# CH595X-R0.net
KiCad netlist of a schematic drawn in Altium Designer
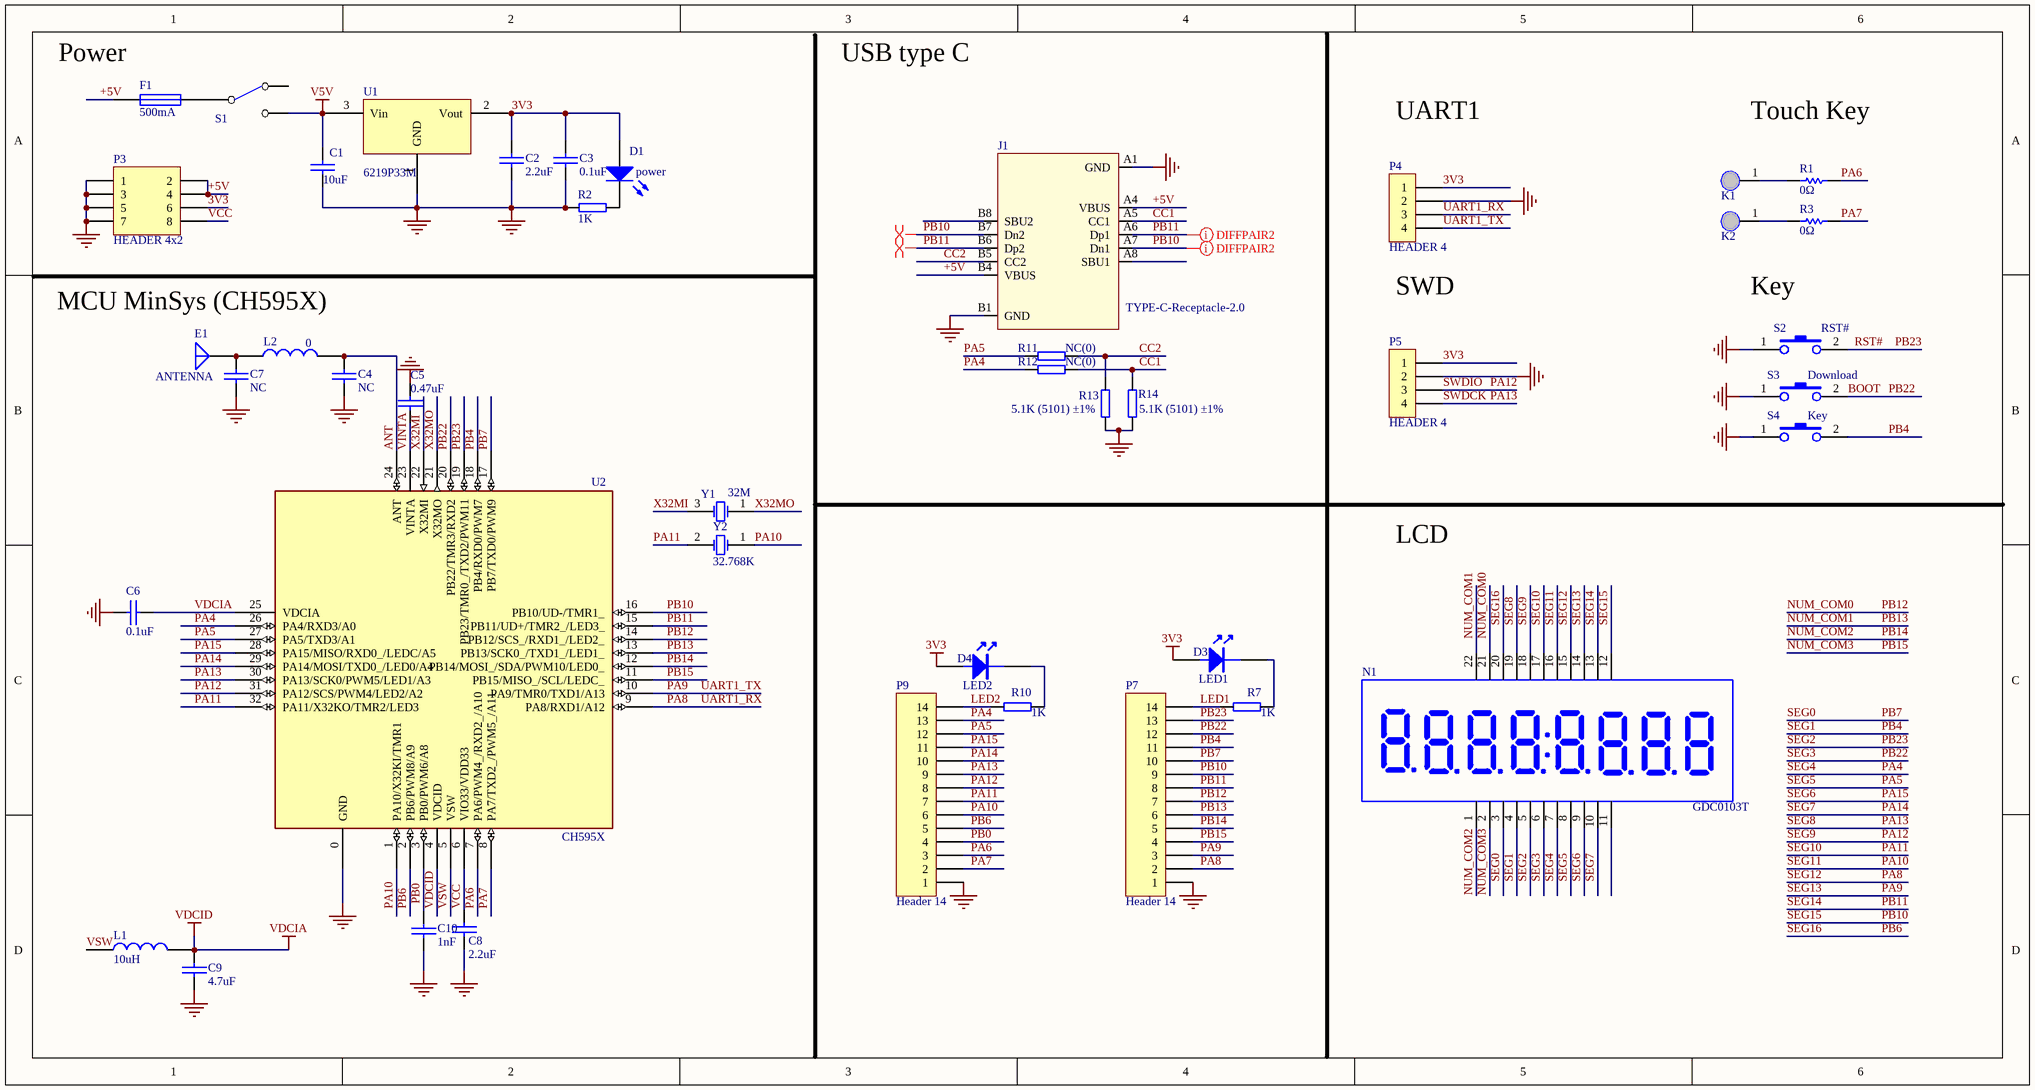
[diagram p0: CH595X-R0.SchDoc]

(export (version "E")
  (design (tool "Eeschema 10.0.6"))
  (components
    (comp (ref "C1")
      (value "10uF")
      (footprint "0603_C")
      (description "Capacitor")
      (libsource (lib "") (part "CAP_1"))
    )
    (comp (ref "C2")
      (value "2.2uF")
      (footprint "0402_C")
      (description "Capacitor")
      (libsource (lib "") (part "CAP_1"))
    )
    (comp (ref "C3")
      (value "0.1uF")
      (footprint "0402_C")
      (description "Capacitor")
      (libsource (lib "") (part "CAP_1"))
    )
    (comp (ref "C4")
      (value "NC")
      (footprint "0402_C")
      (description "Capacitor")
      (libsource (lib "*") (part "CAP"))
    )
    (comp (ref "C5")
      (value "0.47uF")
      (footprint "0402_C")
      (description "Capacitor")
      (libsource (lib "*") (part "CAP"))
    )
    (comp (ref "C6")
      (value "0.1uF")
      (footprint "0402_C")
      (description "Capacitor")
      (libsource (lib "*") (part "CAP"))
    )
    (comp (ref "C7")
      (value "NC")
      (footprint "0402_C")
      (description "Capacitor")
      (libsource (lib "*") (part "CAP"))
    )
    (comp (ref "C8")
      (value "2.2uF")
      (footprint "0402_C")
      (description "Capacitor")
      (libsource (lib "*") (part "CAP"))
    )
    (comp (ref "C9")
      (value "4.7uF")
      (footprint "0402_C")
      (description "Capacitor")
      (libsource (lib "*") (part "CAP"))
    )
    (comp (ref "C10")
      (value "1nF")
      (footprint "0402_C")
      (description "Capacitor")
      (libsource (lib "*") (part "CAP"))
    )
    (comp (ref "D1")
      (value "power")
      (footprint "0603+")
      (description "Typical INFRARED GaAs LED")
      (fields (field (name "PUBLISHER") "Altium Limited"))
      (libsource (lib "*") (part "LED0"))
    )
    (comp (ref "D3") (value "LED1") (footprint "0603+") (libsource (lib "*") (part "LED")))
    (comp (ref "D4") (value "LED2") (footprint "0603+") (libsource (lib "*") (part "LED")))
    (comp (ref "E1")
      (value "ANTENNA")
      (footprint "ANT-F-1-2.4G-1.6mmFR4")
      (description "Generic Antenna")
      (libsource (lib "*") (part "ANTENNA"))
    )
    (comp (ref "F1")
      (value "500mA")
      (footprint "0603")
      (description "Fuse")
      (libsource (lib "wch_sch_others") (part "FUSE1"))
    )
    (comp (ref "J1")
      (value "TYPE-C-Receptacle-2.0")
      (footprint "TYPE-C-Receptacle-2.0")
      (description "Type-C USB2.0 母座")
      (libsource (lib "Miscellaneous SCH Lib") (part "TYPE-C-Receptacle-2.0"))
    )
    (comp (ref "K1")
      (value "TOUCHKEY")
      (footprint "TOUCHKEY-13.6mm-S")
      (libsource (lib "wch_sch_others") (part "TOUCHKEY"))
    )
    (comp (ref "K2")
      (value "TOUCHKEY")
      (footprint "TOUCHKEY-13.6mm-S")
      (libsource (lib "wch_sch_others") (part "TOUCHKEY"))
    )
    (comp (ref "L1") (value "10uH") (footprint "SMD_2x2mm") (libsource (lib "*") (part "INDUCTOR")))
    (comp (ref "L2") (value "0") (footprint "0402") (libsource (lib "*") (part "INDUCTOR")))
    (comp (ref "N1") (value "GDC0103T") (footprint "EDC103") (libsource (lib "*") (part "EDC103")))
    (comp (ref "P3")
      (value "HEADER 4x2")
      (footprint "MYPCB:IDC8-2.54mm")
      (description "Header, 4-Pin, Dual row")
      (libsource (lib "wch_sch_others") (part "HEADER 4x2"))
    )
    (comp (ref "P4")
      (value "HEADER 4")
      (footprint "SIP4-2.54mm")
      (libsource (lib "wch_sch_others") (part "HEADER 4"))
    )
    (comp (ref "P5")
      (value "HEADER 4")
      (footprint "SIP4-2.54mm")
      (libsource (lib "wch_sch_others") (part "HEADER 4"))
    )
    (comp (ref "P7")
      (value "Header 14")
      (footprint "SIP14-2.54mm")
      (description "Header, 14-Pin")
      (fields (field (name "PUBLISHER") "Altium Limited"))
      (libsource (lib "Miscellaneous Connectors") (part "Header 14"))
    )
    (comp (ref "P9")
      (value "Header 14")
      (footprint "SIP14-2.54mm")
      (description "Header, 14-Pin")
      (fields (field (name "PUBLISHER") "Altium Limited"))
      (libsource (lib "Miscellaneous Connectors") (part "Header 14"))
    )
    (comp (ref "R1")
      (value "0Ω")
      (footprint "0402")
      (description "Semiconductor Resistor")
      (fields (field (name "PUBLISHER") "Altium Limited"))
      (libsource (lib "Miscellaneous Devices") (part "Res Semi"))
    )
    (comp (ref "R2") (value "1K") (footprint "0402") (libsource (lib "wch_sch_others") (part "RES")))
    (comp (ref "R3")
      (value "0Ω")
      (footprint "0402")
      (description "Semiconductor Resistor")
      (fields (field (name "PUBLISHER") "Altium Limited"))
      (libsource (lib "Miscellaneous Devices") (part "Res Semi"))
    )
    (comp (ref "R7") (value "1K") (footprint "0402") (libsource (lib "wch_sch_others") (part "RES")))
    (comp (ref "R10") (value "1K") (footprint "0402") (libsource (lib "wch_sch_others") (part "RES")))
    (comp (ref "R11") (value "NC(0)") (footprint "0402") (libsource (lib "wch_sch_others") (part "RES")))
    (comp (ref "R12") (value "NC(0)") (footprint "0402") (libsource (lib "wch_sch_others") (part "RES")))
    (comp (ref "R13")
      (value "5.1K (5101) ±1%")
      (footprint "0402")
      (libsource (lib "wch_sch_others") (part "RES"))
    )
    (comp (ref "R14")
      (value "5.1K (5101) ±1%")
      (footprint "0402")
      (libsource (lib "wch_sch_others") (part "RES"))
    )
    (comp (ref "S1") (value "SW SPDT") (footprint "SW1") (libsource (lib "*") (part "SW SPDT")))
    (comp (ref "S2")
      (value "RST#")
      (footprint "SMD_6.1x3.65x2.5mm-KEY")
      (libsource (lib "wch_sch_others") (part "KEY1"))
    )
    (comp (ref "S3")
      (value "Download")
      (footprint "SMD_6.1x3.65x2.5mm-KEY")
      (libsource (lib "wch_sch_others") (part "KEY1"))
    )
    (comp (ref "S4")
      (value "Key")
      (footprint "SMD_6.1x3.65x2.5mm-KEY")
      (libsource (lib "wch_sch_others") (part "KEY1"))
    )
    (comp (ref "U1")
      (value "6219P33M")
      (footprint "SOT-23")
      (libsource (lib "wch_sch_others") (part "6219P33M"))
    )
    (comp (ref "U2")
      (value "CH595X")
      (footprint "QFN32_4X4")
      (description "RISC-V MCU with BLE/USB/ADC/SPI/4*UART/I2C/LCD/LEDC")
      (libsource (lib "DHXXXSCH") (part "CH595X"))
    )
    (comp (ref "Y1")
      (value "32M")
      (footprint "XT3225")
      (description "Crystal Oscillator")
      (fields (field (name "PUBLISHER") "Altium Limited"))
      (libsource (lib "") (part "XTAL_1"))
    )
    (comp (ref "Y2")
      (value "32.768K")
      (footprint "fc-135")
      (description "Crystal Oscillator")
      (fields (field (name "PUBLISHER") "Altium Limited"))
      (libsource (lib "*") (part "XTAL"))
    )
  )
  (nets
    (net (code "1") (name "/+5V") (class "Default")
      (node (ref "F1") (pin "1") (pinfunction "1_1") (pintype "passive"))
      (node (ref "J1") (pin "A4") (pinfunction "VBUS_A4") (pintype "passive"))
      (node (ref "J1") (pin "B4") (pinfunction "VBUS_B4") (pintype "passive"))
      (node (ref "P3") (pin "2") (pinfunction "2_2") (pintype "passive"))
      (node (ref "P3") (pin "4") (pinfunction "4_4") (pintype "passive"))
    )
    (net (code "2") (name "/ANT") (class "Default")
      (node (ref "C4") (pin "2") (pinfunction "2_2") (pintype "passive"))
      (node (ref "L2") (pin "2") (pinfunction "2_2") (pintype "passive"))
      (node (ref "U2") (pin "24") (pinfunction "ANT_24") (pintype "bidirectional"))
    )
    (net (code "3") (name "/BOOT") (class "Default")
      (node (ref "N1") (pin "6") (pintype "passive"))
      (node (ref "P7") (pin "12") (pinfunction "12_12") (pintype "passive"))
      (node (ref "S3") (pin "2") (pinfunction "2_2") (pintype "passive"))
      (node (ref "U2") (pin "20") (pinfunction "PB22/TMR3/RXD2_20") (pintype "bidirectional"))
    )
    (net (code "4") (name "/CC1") (class "Default")
      (node (ref "J1") (pin "A5") (pinfunction "CC1_A5") (pintype "passive"))
      (node (ref "R12") (pin "2") (pintype "passive"))
      (node (ref "R14") (pin "1") (pintype "passive"))
    )
    (net (code "5") (name "/CC2") (class "Default")
      (node (ref "J1") (pin "B5") (pinfunction "CC2_B5") (pintype "passive"))
      (node (ref "R11") (pin "2") (pintype "passive"))
      (node (ref "R13") (pin "1") (pintype "passive"))
    )
    (net (code "6") (name "/LED1") (class "Default")
      (node (ref "P7") (pin "14") (pinfunction "14_14") (pintype "passive"))
      (node (ref "R7") (pin "1") (pintype "passive"))
    )
    (net (code "7") (name "/LED2") (class "Default")
      (node (ref "P9") (pin "14") (pinfunction "14_14") (pintype "passive"))
      (node (ref "R10") (pin "1") (pintype "passive"))
    )
    (net (code "8") (name "/NUM_COM0") (class "Default")
      (node (ref "N1") (pin "21") (pintype "passive"))
      (node (ref "P7") (pin "7") (pinfunction "7_7") (pintype "passive"))
      (node (ref "U2") (pin "14") (pinfunction "PB12/SCS_/RXD1_/LED2__14") (pintype "bidirectional"))
    )
    (net (code "9") (name "/NUM_COM1") (class "Default")
      (node (ref "N1") (pin "22") (pintype "passive"))
      (node (ref "P7") (pin "6") (pinfunction "6_6") (pintype "passive"))
      (node (ref "U2") (pin "13") (pinfunction "PB13/SCK0_/TXD1_/LED1__13") (pintype "bidirectional"))
    )
    (net (code "10") (name "/NUM_COM2") (class "Default")
      (node (ref "N1") (pin "1") (pintype "passive"))
      (node (ref "P7") (pin "5") (pinfunction "5_5") (pintype "passive"))
      (node (ref "U2") (pin "12") (pinfunction "PB14/MOSI_/SDA/PWM10/LED0__12") (pintype "bidirectional"))
    )
    (net (code "11") (name "/NUM_COM3") (class "Default")
      (node (ref "N1") (pin "2") (pintype "passive"))
      (node (ref "P7") (pin "4") (pinfunction "4_4") (pintype "passive"))
      (node (ref "U2") (pin "11") (pinfunction "PB15/MISO_/SCL/LEDC__11") (pintype "bidirectional"))
    )
    (net (code "12") (name "/PA4") (class "Default")
      (node (ref "N1") (pin "7") (pintype "passive"))
      (node (ref "P9") (pin "13") (pinfunction "13_13") (pintype "passive"))
      (node (ref "R12") (pin "1") (pintype "passive"))
      (node (ref "U2") (pin "26") (pinfunction "PA4/RXD3/A0_26") (pintype "bidirectional"))
    )
    (net (code "13") (name "/PA5") (class "Default")
      (node (ref "N1") (pin "8") (pintype "passive"))
      (node (ref "P9") (pin "12") (pinfunction "12_12") (pintype "passive"))
      (node (ref "R11") (pin "1") (pintype "passive"))
      (node (ref "U2") (pin "27") (pinfunction "PA5/TXD3/A1_27") (pintype "bidirectional"))
    )
    (net (code "14") (name "/PA6") (class "Default")
      (node (ref "P9") (pin "3") (pinfunction "3_3") (pintype "passive"))
      (node (ref "R1") (pin "1") (pinfunction "1_1") (pintype "passive"))
      (node (ref "U2") (pin "7") (pinfunction "PA6/PWM4_/RXD2_/A10_7") (pintype "bidirectional"))
    )
    (net (code "15") (name "/PA7") (class "Default")
      (node (ref "P9") (pin "2") (pinfunction "2_2") (pintype "passive"))
      (node (ref "R3") (pin "1") (pinfunction "1_1") (pintype "passive"))
      (node (ref "U2") (pin "8") (pinfunction "PA7/TXD2_/PWM5_/A11_8") (pintype "bidirectional"))
    )
    (net (code "16") (name "/PA8") (class "Default")
      (node (ref "N1") (pin "15") (pintype "passive"))
      (node (ref "P4") (pin "3") (pinfunction "3_3") (pintype "passive"))
      (node (ref "P7") (pin "2") (pinfunction "2_2") (pintype "passive"))
      (node (ref "U2") (pin "9") (pinfunction "PA8/RXD1/A12_9") (pintype "bidirectional"))
    )
    (net (code "17") (name "/PA9") (class "Default")
      (node (ref "N1") (pin "14") (pintype "passive"))
      (node (ref "P4") (pin "4") (pinfunction "4_4") (pintype "passive"))
      (node (ref "P7") (pin "3") (pinfunction "3_3") (pintype "passive"))
      (node (ref "U2") (pin "10") (pinfunction "PA9/TMR0/TXD1/A13_10") (pintype "bidirectional"))
    )
    (net (code "18") (name "/PA10") (class "Default")
      (node (ref "N1") (pin "16") (pintype "passive"))
      (node (ref "P9") (pin "6") (pinfunction "6_6") (pintype "passive"))
      (node (ref "U2") (pin "1") (pinfunction "PA10/X32KI/TMR1_1") (pintype "bidirectional"))
      (node (ref "Y2") (pin "1") (pinfunction "OSC1_1") (pintype "passive"))
    )
    (net (code "19") (name "/PA11") (class "Default")
      (node (ref "N1") (pin "17") (pintype "passive"))
      (node (ref "P9") (pin "7") (pinfunction "7_7") (pintype "passive"))
      (node (ref "U2") (pin "32") (pinfunction "PA11/X32KO/TMR2/LED3_32") (pintype "bidirectional"))
      (node (ref "Y2") (pin "2") (pinfunction "OSC2_2") (pintype "passive"))
    )
    (net (code "20") (name "/PA12") (class "Default")
      (node (ref "N1") (pin "18") (pintype "passive"))
      (node (ref "P5") (pin "3") (pinfunction "3_3") (pintype "passive"))
      (node (ref "P9") (pin "8") (pinfunction "8_8") (pintype "passive"))
      (node (ref "U2") (pin "31") (pinfunction "PA12/SCS/PWM4/LED2/A2_31") (pintype "bidirectional"))
    )
    (net (code "21") (name "/PA13") (class "Default")
      (node (ref "N1") (pin "19") (pintype "passive"))
      (node (ref "P5") (pin "4") (pinfunction "4_4") (pintype "passive"))
      (node (ref "P9") (pin "9") (pinfunction "9_9") (pintype "passive"))
      (node (ref "U2") (pin "30") (pinfunction "PA13/SCK0/PWM5/LED1/A3_30") (pintype "bidirectional"))
    )
    (net (code "22") (name "/PA14") (class "Default")
      (node (ref "N1") (pin "10") (pintype "passive"))
      (node (ref "P9") (pin "10") (pinfunction "10_10") (pintype "passive"))
      (node (ref "U2") (pin "29") (pinfunction "PA14/MOSI/TXD0_/LED0/A4_29") (pintype "bidirectional"))
    )
    (net (code "23") (name "/PA15") (class "Default")
      (node (ref "N1") (pin "9") (pintype "passive"))
      (node (ref "P9") (pin "11") (pinfunction "11_11") (pintype "passive"))
      (node (ref "U2") (pin "28") (pinfunction "PA15/MISO/RXD0_/LEDC/A5_28") (pintype "bidirectional"))
    )
    (net (code "24") (name "/PB0") (class "Default")
      (node (ref "C10") (pin "2") (pinfunction "2_2") (pintype "passive"))
      (node (ref "P9") (pin "4") (pinfunction "4_4") (pintype "passive"))
      (node (ref "U2") (pin "3") (pinfunction "PB0/PWM6/A8_3") (pintype "bidirectional"))
    )
    (net (code "25") (name "/PB4") (class "Default")
      (node (ref "N1") (pin "4") (pintype "passive"))
      (node (ref "P7") (pin "11") (pinfunction "11_11") (pintype "passive"))
      (node (ref "S4") (pin "2") (pinfunction "2_2") (pintype "passive"))
      (node (ref "U2") (pin "18") (pinfunction "PB4/RXD0/PWM7_18") (pintype "bidirectional"))
    )
    (net (code "26") (name "/PB6") (class "Default")
      (node (ref "N1") (pin "20") (pintype "passive"))
      (node (ref "P9") (pin "5") (pinfunction "5_5") (pintype "passive"))
      (node (ref "U2") (pin "2") (pinfunction "PB6/PWM8/A9_2") (pintype "bidirectional"))
    )
    (net (code "27") (name "/PB7") (class "Default")
      (node (ref "N1") (pin "3") (pintype "passive"))
      (node (ref "P7") (pin "10") (pinfunction "10_10") (pintype "passive"))
      (node (ref "U2") (pin "17") (pinfunction "PB7/TXD0/PWM9_17") (pintype "bidirectional"))
    )
    (net (code "28") (name "/PB10") (class "Default")
      (node (ref "J1") (pin "A7") (pinfunction "Dn1_A7") (pintype "passive"))
      (node (ref "J1") (pin "B7") (pinfunction "Dn2_B7") (pintype "passive"))
      (node (ref "N1") (pin "12") (pintype "passive"))
      (node (ref "P7") (pin "9") (pinfunction "9_9") (pintype "passive"))
      (node (ref "U2") (pin "16") (pinfunction "PB10/UD-/TMR1__16") (pintype "bidirectional"))
    )
    (net (code "29") (name "/PB11") (class "Default")
      (node (ref "J1") (pin "A6") (pinfunction "Dp1_A6") (pintype "passive"))
      (node (ref "J1") (pin "B6") (pinfunction "Dp2_B6") (pintype "passive"))
      (node (ref "N1") (pin "13") (pintype "passive"))
      (node (ref "P7") (pin "8") (pinfunction "8_8") (pintype "passive"))
      (node (ref "U2") (pin "15") (pinfunction "PB11/UD+/TMR2_/LED3__15") (pintype "bidirectional"))
    )
    (net (code "30") (name "/PB23") (class "Default")
      (node (ref "N1") (pin "5") (pintype "passive"))
      (node (ref "P7") (pin "13") (pinfunction "13_13") (pintype "passive"))
      (node (ref "S2") (pin "2") (pinfunction "2_2") (pintype "passive"))
      (node (ref "U2") (pin "19") (pinfunction "PB23/TMR0_/TXD2/PWM11_19") (pintype "bidirectional"))
    )
    (net (code "31") (name "/VCC") (class "Default")
      (node (ref "C8") (pin "2") (pinfunction "2_2") (pintype "passive"))
      (node (ref "P3") (pin "8") (pinfunction "8_8") (pintype "passive"))
      (node (ref "U2") (pin "6") (pinfunction "VIO33/VDD33_6") (pintype "power_in"))
    )
    (net (code "32") (name "/VINTA") (class "Default")
      (node (ref "C5") (pin "1") (pinfunction "1_1") (pintype "passive"))
      (node (ref "U2") (pin "23") (pinfunction "VINTA_23") (pintype "power_in"))
    )
    (net (code "33") (name "/VSW") (class "Default")
      (node (ref "L1") (pin "1") (pinfunction "1_1") (pintype "passive"))
      (node (ref "U2") (pin "5") (pinfunction "VSW_5") (pintype "power_in"))
    )
    (net (code "34") (name "/X32MI") (class "Default")
      (node (ref "U2") (pin "22") (pinfunction "X32MI_22") (pintype "input"))
      (node (ref "Y1") (pin "3") (pinfunction "OSC2_3") (pintype "passive"))
    )
    (net (code "35") (name "/X32MO") (class "Default")
      (node (ref "U2") (pin "21") (pinfunction "X32MO_21") (pintype "output"))
      (node (ref "Y1") (pin "1") (pinfunction "OSC1_1") (pintype "passive"))
    )
    (net (code "36") (name "3V3") (class "Default")
      (node (ref "C2") (pin "1") (pinfunction "1_1") (pintype "passive"))
      (node (ref "C3") (pin "1") (pinfunction "1_1") (pintype "passive"))
      (node (ref "D1") (pin "1") (pinfunction "A_1") (pintype "passive"))
      (node (ref "D3") (pin "1") (pinfunction "1_1") (pintype "passive"))
      (node (ref "D4") (pin "1") (pinfunction "1_1") (pintype "passive"))
      (node (ref "P3") (pin "6") (pinfunction "6_6") (pintype "passive"))
      (node (ref "P4") (pin "1") (pinfunction "1_1") (pintype "passive"))
      (node (ref "P5") (pin "1") (pinfunction "1_1") (pintype "passive"))
      (node (ref "U1") (pin "2") (pinfunction "Vout_2") (pintype "passive"))
    )
    (net (code "37") (name "GND") (class "Default")
      (node (ref "C1") (pin "2") (pinfunction "2_2") (pintype "passive"))
      (node (ref "C10") (pin "1") (pinfunction "1_1") (pintype "passive"))
      (node (ref "C2") (pin "2") (pinfunction "2_2") (pintype "passive"))
      (node (ref "C3") (pin "2") (pinfunction "2_2") (pintype "passive"))
      (node (ref "C4") (pin "1") (pinfunction "1_1") (pintype "passive"))
      (node (ref "C5") (pin "2") (pinfunction "2_2") (pintype "passive"))
      (node (ref "C6") (pin "2") (pinfunction "2_2") (pintype "passive"))
      (node (ref "C7") (pin "1") (pinfunction "1_1") (pintype "passive"))
      (node (ref "C8") (pin "1") (pinfunction "1_1") (pintype "passive"))
      (node (ref "C9") (pin "1") (pinfunction "1_1") (pintype "passive"))
      (node (ref "J1") (pin "A1") (pinfunction "GND_A1") (pintype "passive"))
      (node (ref "J1") (pin "B1") (pinfunction "GND_B1") (pintype "passive"))
      (node (ref "P3") (pin "1") (pinfunction "1_1") (pintype "passive"))
      (node (ref "P3") (pin "3") (pinfunction "3_3") (pintype "passive"))
      (node (ref "P3") (pin "5") (pinfunction "5_5") (pintype "passive"))
      (node (ref "P3") (pin "7") (pinfunction "7_7") (pintype "passive"))
      (node (ref "P4") (pin "2") (pinfunction "2_2") (pintype "passive"))
      (node (ref "P5") (pin "2") (pinfunction "2_2") (pintype "passive"))
      (node (ref "P7") (pin "1") (pinfunction "1_1") (pintype "passive"))
      (node (ref "P9") (pin "1") (pinfunction "1_1") (pintype "passive"))
      (node (ref "R13") (pin "2") (pintype "passive"))
      (node (ref "R14") (pin "2") (pintype "passive"))
      (node (ref "R2") (pin "2") (pintype "passive"))
      (node (ref "S2") (pin "1") (pinfunction "1_1") (pintype "passive"))
      (node (ref "S3") (pin "1") (pinfunction "1_1") (pintype "passive"))
      (node (ref "S4") (pin "1") (pinfunction "1_1") (pintype "passive"))
      (node (ref "U1") (pin "1") (pinfunction "GND_1") (pintype "passive"))
      (node (ref "U2") (pin "0") (pinfunction "GND_0") (pintype "power_in"))
    )
    (net (code "38") (name "Net-(D1-K)") (class "Default")
      (node (ref "D1") (pin "2") (pinfunction "K_2") (pintype "passive"))
      (node (ref "R2") (pin "1") (pintype "passive"))
    )
    (net (code "39") (name "Net-(D3-Pad2)") (class "Default")
      (node (ref "D3") (pin "2") (pinfunction "2_2") (pintype "passive"))
      (node (ref "R7") (pin "2") (pintype "passive"))
    )
    (net (code "40") (name "Net-(D4-Pad2)") (class "Default")
      (node (ref "D4") (pin "2") (pinfunction "2_2") (pintype "passive"))
      (node (ref "R10") (pin "2") (pintype "passive"))
    )
    (net (code "41") (name "Net-(E1-A)") (class "Default")
      (node (ref "C7") (pin "2") (pinfunction "2_2") (pintype "passive"))
      (node (ref "E1") (pin "1") (pinfunction "A_1") (pintype "passive"))
      (node (ref "L2") (pin "1") (pinfunction "1_1") (pintype "passive"))
    )
    (net (code "42") (name "Net-(K1-Pad1)") (class "Default")
      (node (ref "K1") (pin "1") (pintype "passive"))
      (node (ref "R1") (pin "2") (pinfunction "2_2") (pintype "passive"))
    )
    (net (code "43") (name "Net-(K2-Pad1)") (class "Default")
      (node (ref "K2") (pin "1") (pintype "passive"))
      (node (ref "R3") (pin "2") (pinfunction "2_2") (pintype "passive"))
    )
    (net (code "44") (name "Net-(S1-COMMON)") (class "Default")
      (node (ref "F1") (pin "2") (pinfunction "2_2") (pintype "passive"))
      (node (ref "S1") (pin "1") (pinfunction "COMMON_1") (pintype "passive"))
    )
    (net (code "45") (name "V5V") (class "Default")
      (node (ref "C1") (pin "1") (pinfunction "1_1") (pintype "passive"))
      (node (ref "S1") (pin "2") (pinfunction "NC_2") (pintype "passive"))
      (node (ref "U1") (pin "3") (pinfunction "Vin_3") (pintype "passive"))
    )
    (net (code "46") (name "VDCIA") (class "Default")
      (node (ref "C6") (pin "1") (pinfunction "1_1") (pintype "passive"))
      (node (ref "C9") (pin "2") (pinfunction "2_2") (pintype "passive"))
      (node (ref "L1") (pin "2") (pinfunction "2_2") (pintype "passive"))
      (node (ref "U2") (pin "25") (pinfunction "VDCIA_25") (pintype "power_in"))
      (node (ref "U2") (pin "4") (pinfunction "VDCID_4") (pintype "power_in"))
    )
    (net (code "47") (name "unconnected-(J1-SBU1-PadA8)") (class "Default")
      (node (ref "J1") (pin "A8") (pinfunction "SBU1_A8") (pintype "passive"))
    )
    (net (code "48") (name "unconnected-(J1-SBU2-PadB8)") (class "Default")
      (node (ref "J1") (pin "B8") (pinfunction "SBU2_B8") (pintype "passive"))
    )
    (net (code "49") (name "unconnected-(N1-Pad11)") (class "Default")
      (node (ref "N1") (pin "11") (pintype "passive"))
    )
    (net (code "50") (name "unconnected-(S1-NO-Pad3)") (class "Default")
      (node (ref "S1") (pin "3") (pinfunction "NO_3") (pintype "passive"))
    )
  )
)
